# main.net
KiCad netlist of a schematic drawn in Altium Designer
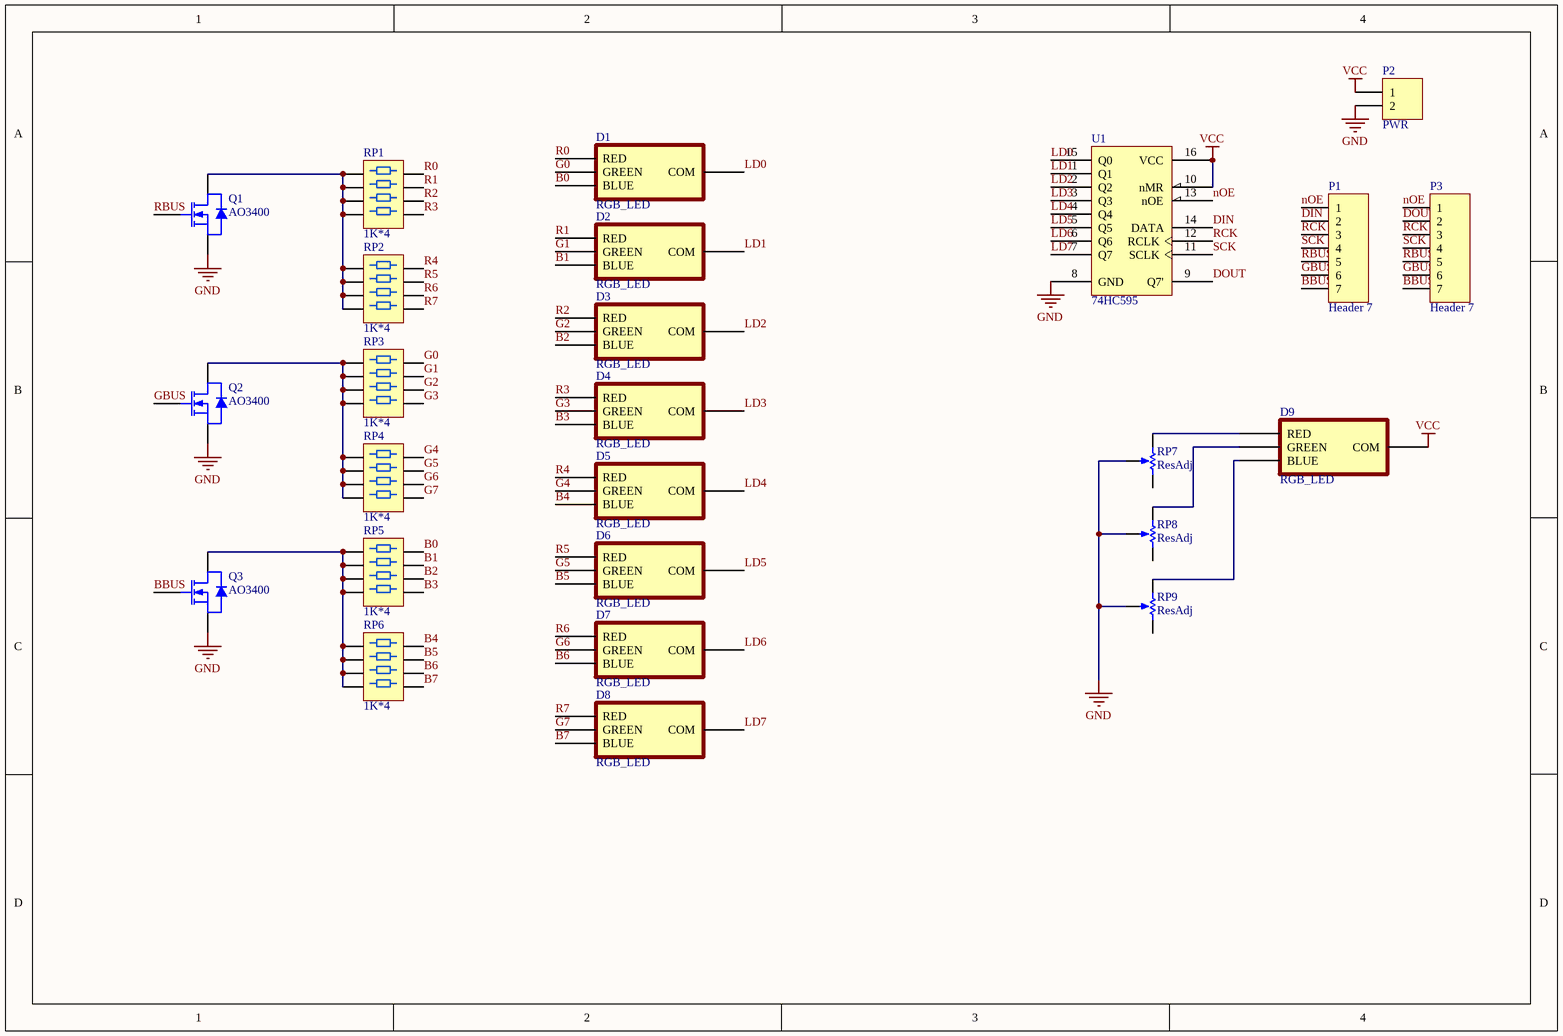
[diagram p0: main.SchDoc]

(export (version "E")
  (design (tool "Eeschema 10.0.6"))
  (components
    (comp (ref "D1")
      (value "RGB_LED")
      (footprint "0805_RGB")
      (libsource (lib "ntw_oldschlib") (part "RGBLED"))
    )
    (comp (ref "D2")
      (value "RGB_LED")
      (footprint "0805_RGB")
      (libsource (lib "ntw_oldschlib") (part "RGBLED"))
    )
    (comp (ref "D3")
      (value "RGB_LED")
      (footprint "0805_RGB")
      (libsource (lib "ntw_oldschlib") (part "RGBLED"))
    )
    (comp (ref "D4")
      (value "RGB_LED")
      (footprint "0805_RGB")
      (libsource (lib "ntw_oldschlib") (part "RGBLED"))
    )
    (comp (ref "D5")
      (value "RGB_LED")
      (footprint "0805_RGB")
      (libsource (lib "ntw_oldschlib") (part "RGBLED"))
    )
    (comp (ref "D6")
      (value "RGB_LED")
      (footprint "0805_RGB")
      (libsource (lib "ntw_oldschlib") (part "RGBLED"))
    )
    (comp (ref "D7")
      (value "RGB_LED")
      (footprint "0805_RGB")
      (libsource (lib "ntw_oldschlib") (part "RGBLED"))
    )
    (comp (ref "D8")
      (value "RGB_LED")
      (footprint "0805_RGB")
      (libsource (lib "ntw_oldschlib") (part "RGBLED"))
    )
    (comp (ref "D9")
      (value "RGB_LED")
      (footprint "0805_RGB")
      (libsource (lib "ntw_oldschlib") (part "RGBLED"))
    )
    (comp (ref "P1")
      (value "Header 7")
      (footprint "HDR1X7")
      (description "Header, 7-Pin")
      (fields (field (name "PUBLISHER") "Altium Limited"))
      (libsource (lib "Miscellaneous Connectors") (part "Header 7"))
    )
    (comp (ref "P2")
      (value "PWR")
      (footprint "HDR1X2")
      (description "Header, 2-Pin")
      (fields (field (name "PUBLISHER") "Altium Limited"))
      (libsource (lib "Miscellaneous Connectors") (part "Header 2"))
    )
    (comp (ref "P3")
      (value "Header 7")
      (footprint "HDR1X7")
      (description "Header, 7-Pin")
      (fields (field (name "PUBLISHER") "Altium Limited"))
      (libsource (lib "Miscellaneous Connectors") (part "Header 7"))
    )
    (comp (ref "Q1")
      (value "AO3400")
      (footprint "SOT-23")
      (description "N-Channel MOSFET")
      (fields (field (name "PUBLISHER") "Altium Limited"))
      (libsource (lib "ntw_oldschlib") (part "AO3400"))
    )
    (comp (ref "Q2")
      (value "AO3400")
      (footprint "SOT-23")
      (description "N-Channel MOSFET")
      (fields (field (name "PUBLISHER") "Altium Limited"))
      (libsource (lib "ntw_oldschlib") (part "AO3400"))
    )
    (comp (ref "Q3")
      (value "AO3400")
      (footprint "SOT-23")
      (description "N-Channel MOSFET")
      (fields (field (name "PUBLISHER") "Altium Limited"))
      (libsource (lib "ntw_oldschlib") (part "AO3400"))
    )
    (comp (ref "RP1") (value "1K*4") (footprint "0603x4") (libsource (lib "ntw_oldschlib") (part "RPack_4")))
    (comp (ref "RP2") (value "1K*4") (footprint "0603x4") (libsource (lib "ntw_oldschlib") (part "RPack_4")))
    (comp (ref "RP3") (value "1K*4") (footprint "0603x4") (libsource (lib "ntw_oldschlib") (part "RPack_4")))
    (comp (ref "RP4") (value "1K*4") (footprint "0603x4") (libsource (lib "ntw_oldschlib") (part "RPack_4")))
    (comp (ref "RP5") (value "1K*4") (footprint "0603x4") (libsource (lib "ntw_oldschlib") (part "RPack_4")))
    (comp (ref "RP6") (value "1K*4") (footprint "0603x4") (libsource (lib "ntw_oldschlib") (part "RPack_4")))
    (comp (ref "RP7")
      (value "ResAdj")
      (footprint "RP_POT")
      (description "Potentiometer")
      (fields (field (name "PUBLISHER") "Altium Limited"))
      (libsource (lib "ntw_oldschlib") (part "RPot"))
    )
    (comp (ref "RP8")
      (value "ResAdj")
      (footprint "RP_POT")
      (description "Potentiometer")
      (fields (field (name "PUBLISHER") "Altium Limited"))
      (libsource (lib "ntw_oldschlib") (part "RPot"))
    )
    (comp (ref "RP9")
      (value "ResAdj")
      (footprint "RP_POT")
      (description "Potentiometer")
      (fields (field (name "PUBLISHER") "Altium Limited"))
      (libsource (lib "ntw_oldschlib") (part "RPot"))
    )
    (comp (ref "U1")
      (value "74HC595")
      (footprint "TSSOP16")
      (description "8-bit serial-in, serial or parallel-out shift register with output latches; 3-state")
      (libsource (lib "ntw_oldschlib") (part "74HC595"))
    )
  )
  (nets
    (net (code "1") (name "/B0") (class "Default")
      (node (ref "D1") (pin "B") (pinfunction "BLUE_B") (pintype "passive"))
      (node (ref "RP5") (pin "8") (pinfunction "8_8") (pintype "passive"))
    )
    (net (code "2") (name "/B1") (class "Default")
      (node (ref "D2") (pin "B") (pinfunction "BLUE_B") (pintype "passive"))
      (node (ref "RP5") (pin "7") (pinfunction "7_7") (pintype "passive"))
    )
    (net (code "3") (name "/B2") (class "Default")
      (node (ref "D3") (pin "B") (pinfunction "BLUE_B") (pintype "passive"))
      (node (ref "RP5") (pin "6") (pinfunction "6_6") (pintype "passive"))
    )
    (net (code "4") (name "/B3") (class "Default")
      (node (ref "D4") (pin "B") (pinfunction "BLUE_B") (pintype "passive"))
      (node (ref "RP5") (pin "5") (pinfunction "5_5") (pintype "passive"))
    )
    (net (code "5") (name "/B4") (class "Default")
      (node (ref "D5") (pin "B") (pinfunction "BLUE_B") (pintype "passive"))
      (node (ref "RP6") (pin "8") (pinfunction "8_8") (pintype "passive"))
    )
    (net (code "6") (name "/B5") (class "Default")
      (node (ref "D6") (pin "B") (pinfunction "BLUE_B") (pintype "passive"))
      (node (ref "RP6") (pin "7") (pinfunction "7_7") (pintype "passive"))
    )
    (net (code "7") (name "/B6") (class "Default")
      (node (ref "D7") (pin "B") (pinfunction "BLUE_B") (pintype "passive"))
      (node (ref "RP6") (pin "6") (pinfunction "6_6") (pintype "passive"))
    )
    (net (code "8") (name "/B7") (class "Default")
      (node (ref "D8") (pin "B") (pinfunction "BLUE_B") (pintype "passive"))
      (node (ref "RP6") (pin "5") (pinfunction "5_5") (pintype "passive"))
    )
    (net (code "9") (name "/BBUS") (class "Default")
      (node (ref "P1") (pin "7") (pinfunction "7_7") (pintype "passive"))
      (node (ref "P3") (pin "7") (pinfunction "7_7") (pintype "passive"))
      (node (ref "Q3") (pin "1") (pinfunction "G_1") (pintype "passive"))
    )
    (net (code "10") (name "/DIN") (class "Default")
      (node (ref "P1") (pin "2") (pinfunction "2_2") (pintype "passive"))
      (node (ref "U1") (pin "14") (pinfunction "DATA_14") (pintype "passive"))
    )
    (net (code "11") (name "/DOUT") (class "Default")
      (node (ref "P3") (pin "2") (pinfunction "2_2") (pintype "passive"))
      (node (ref "U1") (pin "9") (pinfunction "Q7'_9") (pintype "passive"))
    )
    (net (code "12") (name "/G0") (class "Default")
      (node (ref "D1") (pin "G") (pinfunction "GREEN_G") (pintype "passive"))
      (node (ref "RP3") (pin "8") (pinfunction "8_8") (pintype "passive"))
    )
    (net (code "13") (name "/G1") (class "Default")
      (node (ref "D2") (pin "G") (pinfunction "GREEN_G") (pintype "passive"))
      (node (ref "RP3") (pin "7") (pinfunction "7_7") (pintype "passive"))
    )
    (net (code "14") (name "/G2") (class "Default")
      (node (ref "D3") (pin "G") (pinfunction "GREEN_G") (pintype "passive"))
      (node (ref "RP3") (pin "6") (pinfunction "6_6") (pintype "passive"))
    )
    (net (code "15") (name "/G3") (class "Default")
      (node (ref "D4") (pin "G") (pinfunction "GREEN_G") (pintype "passive"))
      (node (ref "RP3") (pin "5") (pinfunction "5_5") (pintype "passive"))
    )
    (net (code "16") (name "/G4") (class "Default")
      (node (ref "D5") (pin "G") (pinfunction "GREEN_G") (pintype "passive"))
      (node (ref "RP4") (pin "8") (pinfunction "8_8") (pintype "passive"))
    )
    (net (code "17") (name "/G5") (class "Default")
      (node (ref "D6") (pin "G") (pinfunction "GREEN_G") (pintype "passive"))
      (node (ref "RP4") (pin "7") (pinfunction "7_7") (pintype "passive"))
    )
    (net (code "18") (name "/G6") (class "Default")
      (node (ref "D7") (pin "G") (pinfunction "GREEN_G") (pintype "passive"))
      (node (ref "RP4") (pin "6") (pinfunction "6_6") (pintype "passive"))
    )
    (net (code "19") (name "/G7") (class "Default")
      (node (ref "D8") (pin "G") (pinfunction "GREEN_G") (pintype "passive"))
      (node (ref "RP4") (pin "5") (pinfunction "5_5") (pintype "passive"))
    )
    (net (code "20") (name "/GBUS") (class "Default")
      (node (ref "P1") (pin "6") (pinfunction "6_6") (pintype "passive"))
      (node (ref "P3") (pin "6") (pinfunction "6_6") (pintype "passive"))
      (node (ref "Q2") (pin "1") (pinfunction "G_1") (pintype "passive"))
    )
    (net (code "21") (name "/LD0") (class "Default")
      (node (ref "D1") (pin "COM") (pinfunction "COM_COM") (pintype "passive"))
      (node (ref "U1") (pin "15") (pinfunction "Q0_15") (pintype "passive"))
    )
    (net (code "22") (name "/LD1") (class "Default")
      (node (ref "D2") (pin "COM") (pinfunction "COM_COM") (pintype "passive"))
      (node (ref "U1") (pin "1") (pinfunction "Q1_1") (pintype "passive"))
    )
    (net (code "23") (name "/LD2") (class "Default")
      (node (ref "D3") (pin "COM") (pinfunction "COM_COM") (pintype "passive"))
      (node (ref "U1") (pin "2") (pinfunction "Q2_2") (pintype "passive"))
    )
    (net (code "24") (name "/LD3") (class "Default")
      (node (ref "D4") (pin "COM") (pinfunction "COM_COM") (pintype "passive"))
      (node (ref "U1") (pin "3") (pinfunction "Q3_3") (pintype "passive"))
    )
    (net (code "25") (name "/LD4") (class "Default")
      (node (ref "D5") (pin "COM") (pinfunction "COM_COM") (pintype "passive"))
      (node (ref "U1") (pin "4") (pinfunction "Q4_4") (pintype "passive"))
    )
    (net (code "26") (name "/LD5") (class "Default")
      (node (ref "D6") (pin "COM") (pinfunction "COM_COM") (pintype "passive"))
      (node (ref "U1") (pin "5") (pinfunction "Q5_5") (pintype "passive"))
    )
    (net (code "27") (name "/LD6") (class "Default")
      (node (ref "D7") (pin "COM") (pinfunction "COM_COM") (pintype "passive"))
      (node (ref "U1") (pin "6") (pinfunction "Q6_6") (pintype "passive"))
    )
    (net (code "28") (name "/LD7") (class "Default")
      (node (ref "D8") (pin "COM") (pinfunction "COM_COM") (pintype "passive"))
      (node (ref "U1") (pin "7") (pinfunction "Q7_7") (pintype "passive"))
    )
    (net (code "29") (name "/R0") (class "Default")
      (node (ref "D1") (pin "R") (pinfunction "RED_R") (pintype "passive"))
      (node (ref "RP1") (pin "8") (pinfunction "8_8") (pintype "passive"))
    )
    (net (code "30") (name "/R1") (class "Default")
      (node (ref "D2") (pin "R") (pinfunction "RED_R") (pintype "passive"))
      (node (ref "RP1") (pin "7") (pinfunction "7_7") (pintype "passive"))
    )
    (net (code "31") (name "/R2") (class "Default")
      (node (ref "D3") (pin "R") (pinfunction "RED_R") (pintype "passive"))
      (node (ref "RP1") (pin "6") (pinfunction "6_6") (pintype "passive"))
    )
    (net (code "32") (name "/R3") (class "Default")
      (node (ref "D4") (pin "R") (pinfunction "RED_R") (pintype "passive"))
      (node (ref "RP1") (pin "5") (pinfunction "5_5") (pintype "passive"))
    )
    (net (code "33") (name "/R4") (class "Default")
      (node (ref "D5") (pin "R") (pinfunction "RED_R") (pintype "passive"))
      (node (ref "RP2") (pin "8") (pinfunction "8_8") (pintype "passive"))
    )
    (net (code "34") (name "/R5") (class "Default")
      (node (ref "D6") (pin "R") (pinfunction "RED_R") (pintype "passive"))
      (node (ref "RP2") (pin "7") (pinfunction "7_7") (pintype "passive"))
    )
    (net (code "35") (name "/R6") (class "Default")
      (node (ref "D7") (pin "R") (pinfunction "RED_R") (pintype "passive"))
      (node (ref "RP2") (pin "6") (pinfunction "6_6") (pintype "passive"))
    )
    (net (code "36") (name "/R7") (class "Default")
      (node (ref "D8") (pin "R") (pinfunction "RED_R") (pintype "passive"))
      (node (ref "RP2") (pin "5") (pinfunction "5_5") (pintype "passive"))
    )
    (net (code "37") (name "/RBUS") (class "Default")
      (node (ref "P1") (pin "5") (pinfunction "5_5") (pintype "passive"))
      (node (ref "P3") (pin "5") (pinfunction "5_5") (pintype "passive"))
      (node (ref "Q1") (pin "1") (pinfunction "G_1") (pintype "passive"))
    )
    (net (code "38") (name "/RCK") (class "Default")
      (node (ref "P1") (pin "3") (pinfunction "3_3") (pintype "passive"))
      (node (ref "P3") (pin "3") (pinfunction "3_3") (pintype "passive"))
      (node (ref "U1") (pin "12") (pinfunction "RCLK_12") (pintype "passive"))
    )
    (net (code "39") (name "/SCK") (class "Default")
      (node (ref "P1") (pin "4") (pinfunction "4_4") (pintype "passive"))
      (node (ref "P3") (pin "4") (pinfunction "4_4") (pintype "passive"))
      (node (ref "U1") (pin "11") (pinfunction "SCLK_11") (pintype "passive"))
    )
    (net (code "40") (name "/nOE") (class "Default")
      (node (ref "P1") (pin "1") (pinfunction "1_1") (pintype "passive"))
      (node (ref "P3") (pin "1") (pinfunction "1_1") (pintype "passive"))
      (node (ref "U1") (pin "13") (pinfunction "nOE_13") (pintype "passive"))
    )
    (net (code "41") (name "GND") (class "Default")
      (node (ref "P2") (pin "2") (pinfunction "2_2") (pintype "passive"))
      (node (ref "Q1") (pin "2") (pinfunction "S_2") (pintype "passive"))
      (node (ref "Q2") (pin "2") (pinfunction "S_2") (pintype "passive"))
      (node (ref "Q3") (pin "2") (pinfunction "S_2") (pintype "passive"))
      (node (ref "RP7") (pin "2") (pinfunction "TAP_2") (pintype "passive"))
      (node (ref "RP8") (pin "2") (pinfunction "TAP_2") (pintype "passive"))
      (node (ref "RP9") (pin "2") (pinfunction "TAP_2") (pintype "passive"))
      (node (ref "U1") (pin "8") (pinfunction "GND_8") (pintype "passive"))
    )
    (net (code "42") (name "Net-(D9-BLUE)") (class "Default")
      (node (ref "D9") (pin "B") (pinfunction "BLUE_B") (pintype "passive"))
      (node (ref "RP9") (pin "1") (pinfunction "TOP_1") (pintype "passive"))
    )
    (net (code "43") (name "Net-(D9-GREEN)") (class "Default")
      (node (ref "D9") (pin "G") (pinfunction "GREEN_G") (pintype "passive"))
      (node (ref "RP8") (pin "1") (pinfunction "TOP_1") (pintype "passive"))
    )
    (net (code "44") (name "Net-(D9-RED)") (class "Default")
      (node (ref "D9") (pin "R") (pinfunction "RED_R") (pintype "passive"))
      (node (ref "RP7") (pin "1") (pinfunction "TOP_1") (pintype "passive"))
    )
    (net (code "45") (name "Net-(Q1-D)") (class "Default")
      (node (ref "Q1") (pin "3") (pinfunction "D_3") (pintype "passive"))
      (node (ref "RP1") (pin "1") (pinfunction "1_1") (pintype "passive"))
      (node (ref "RP1") (pin "2") (pinfunction "2_2") (pintype "passive"))
      (node (ref "RP1") (pin "3") (pinfunction "3_3") (pintype "passive"))
      (node (ref "RP1") (pin "4") (pinfunction "4_4") (pintype "passive"))
      (node (ref "RP2") (pin "1") (pinfunction "1_1") (pintype "passive"))
      (node (ref "RP2") (pin "2") (pinfunction "2_2") (pintype "passive"))
      (node (ref "RP2") (pin "3") (pinfunction "3_3") (pintype "passive"))
      (node (ref "RP2") (pin "4") (pinfunction "4_4") (pintype "passive"))
    )
    (net (code "46") (name "Net-(Q2-D)") (class "Default")
      (node (ref "Q2") (pin "3") (pinfunction "D_3") (pintype "passive"))
      (node (ref "RP3") (pin "1") (pinfunction "1_1") (pintype "passive"))
      (node (ref "RP3") (pin "2") (pinfunction "2_2") (pintype "passive"))
      (node (ref "RP3") (pin "3") (pinfunction "3_3") (pintype "passive"))
      (node (ref "RP3") (pin "4") (pinfunction "4_4") (pintype "passive"))
      (node (ref "RP4") (pin "1") (pinfunction "1_1") (pintype "passive"))
      (node (ref "RP4") (pin "2") (pinfunction "2_2") (pintype "passive"))
      (node (ref "RP4") (pin "3") (pinfunction "3_3") (pintype "passive"))
      (node (ref "RP4") (pin "4") (pinfunction "4_4") (pintype "passive"))
    )
    (net (code "47") (name "Net-(Q3-D)") (class "Default")
      (node (ref "Q3") (pin "3") (pinfunction "D_3") (pintype "passive"))
      (node (ref "RP5") (pin "1") (pinfunction "1_1") (pintype "passive"))
      (node (ref "RP5") (pin "2") (pinfunction "2_2") (pintype "passive"))
      (node (ref "RP5") (pin "3") (pinfunction "3_3") (pintype "passive"))
      (node (ref "RP5") (pin "4") (pinfunction "4_4") (pintype "passive"))
      (node (ref "RP6") (pin "1") (pinfunction "1_1") (pintype "passive"))
      (node (ref "RP6") (pin "2") (pinfunction "2_2") (pintype "passive"))
      (node (ref "RP6") (pin "3") (pinfunction "3_3") (pintype "passive"))
      (node (ref "RP6") (pin "4") (pinfunction "4_4") (pintype "passive"))
    )
    (net (code "48") (name "VCC") (class "Default")
      (node (ref "D9") (pin "COM") (pinfunction "COM_COM") (pintype "passive"))
      (node (ref "P2") (pin "1") (pinfunction "1_1") (pintype "passive"))
      (node (ref "U1") (pin "10") (pinfunction "nMR_10") (pintype "passive"))
      (node (ref "U1") (pin "16") (pinfunction "VCC_16") (pintype "passive"))
    )
    (net (code "49") (name "unconnected-(RP7-BOT-Pad3)") (class "Default")
      (node (ref "RP7") (pin "3") (pinfunction "BOT_3") (pintype "passive"))
    )
    (net (code "50") (name "unconnected-(RP8-BOT-Pad3)") (class "Default")
      (node (ref "RP8") (pin "3") (pinfunction "BOT_3") (pintype "passive"))
    )
    (net (code "51") (name "unconnected-(RP9-BOT-Pad3)") (class "Default")
      (node (ref "RP9") (pin "3") (pinfunction "BOT_3") (pintype "passive"))
    )
  )
)
